# Schematic.net
KiCad netlist of a schematic drawn in EAGLE
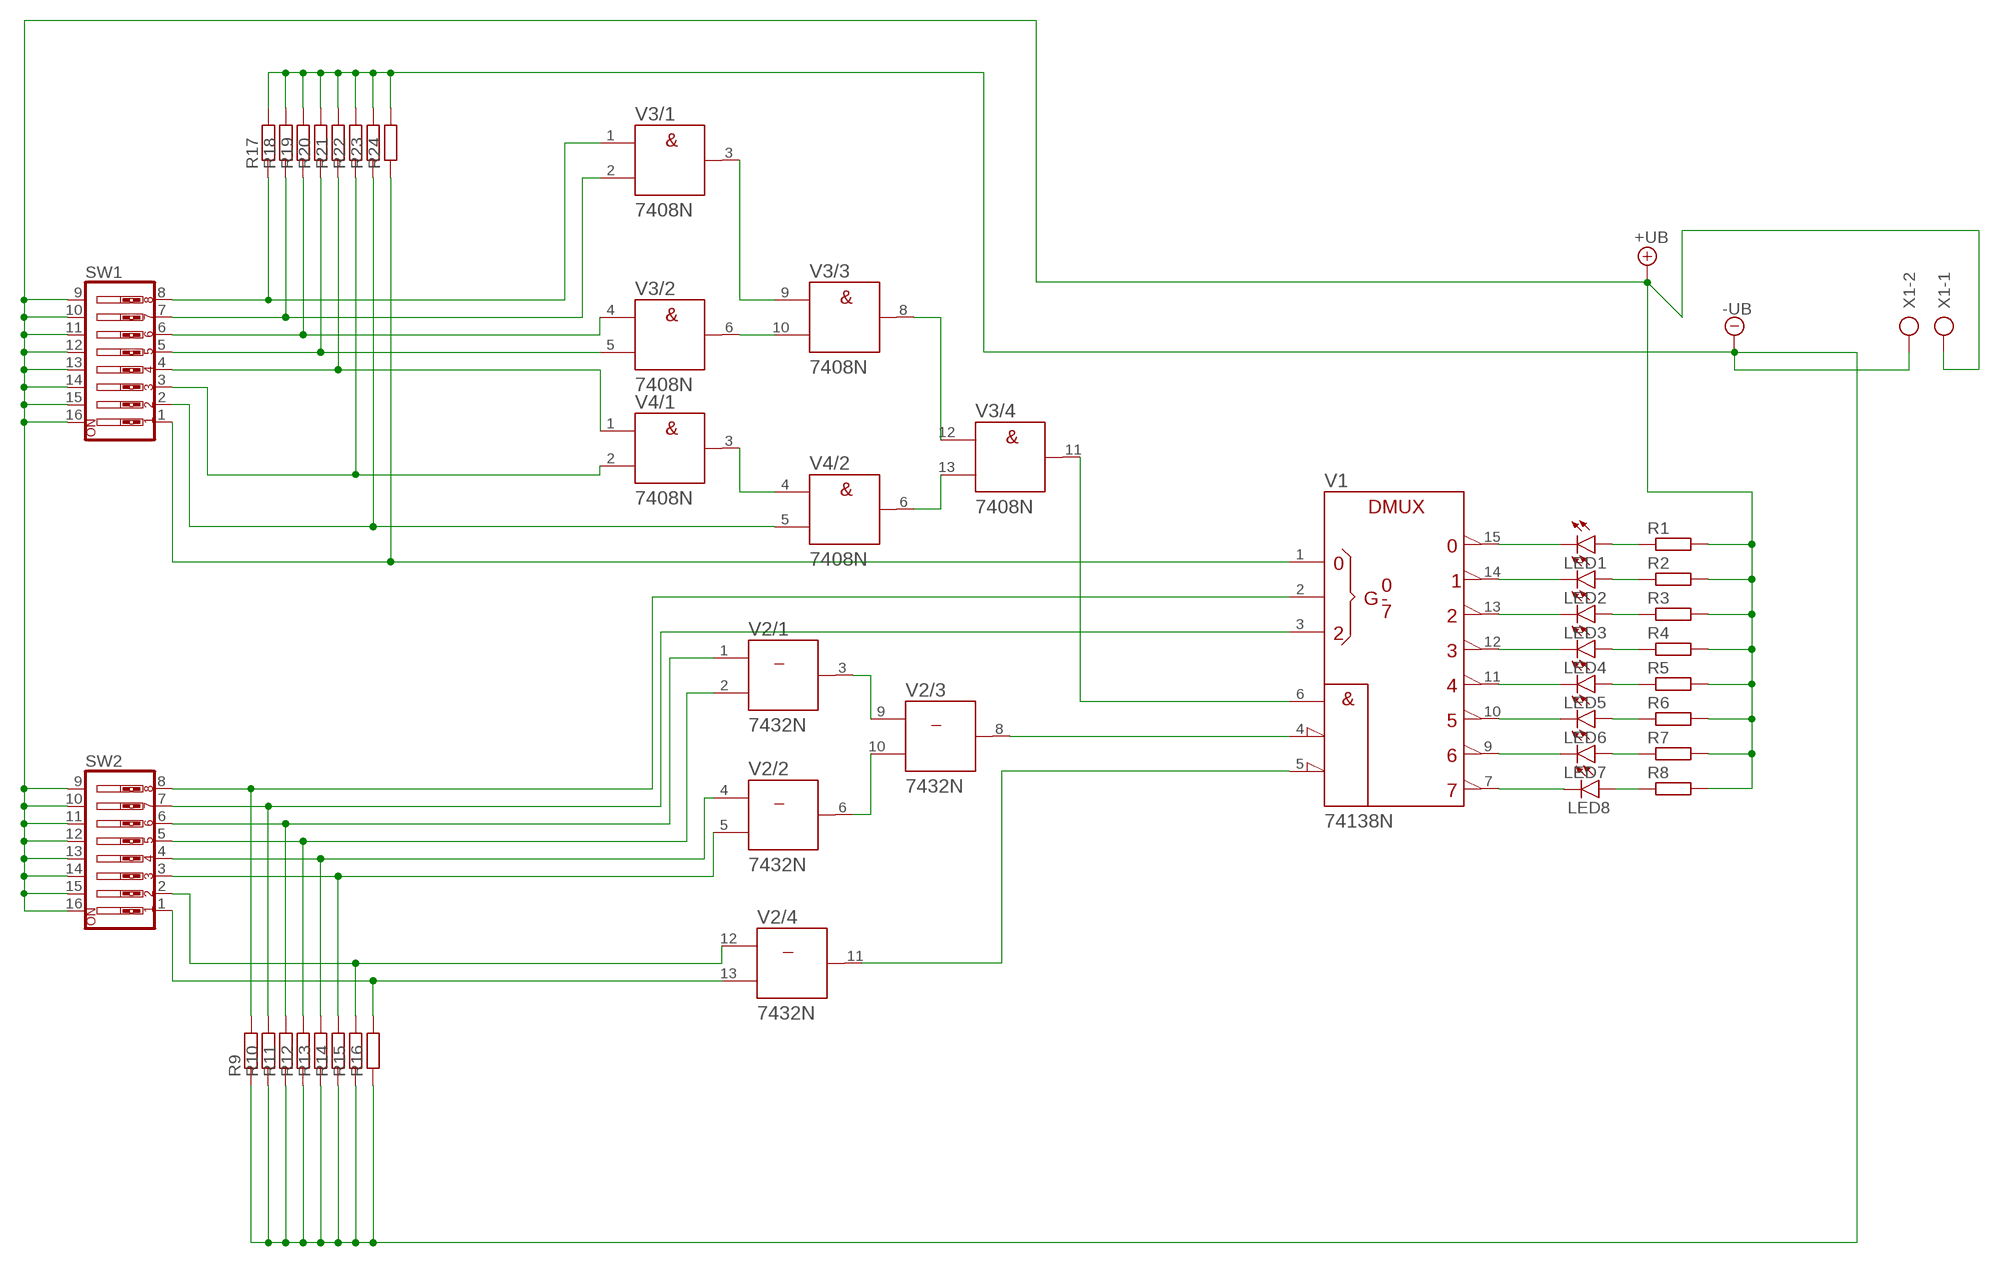
[diagram p0: schematic, sheet 1]

(export (version "E")
  (design (tool "Eeschema 10.0.6"))
  (components
    (comp (ref "LED1")
      (value "LED5MM")
      (footprint "eagle-import:LED5MM")
      (libsource (lib "eagle-import") (part "LED5MM"))
    )
    (comp (ref "LED2")
      (value "LED5MM")
      (footprint "eagle-import:LED5MM")
      (libsource (lib "eagle-import") (part "LED5MM"))
    )
    (comp (ref "LED3")
      (value "LED5MM")
      (footprint "eagle-import:LED5MM")
      (libsource (lib "eagle-import") (part "LED5MM"))
    )
    (comp (ref "LED4")
      (value "LED5MM")
      (footprint "eagle-import:LED5MM")
      (libsource (lib "eagle-import") (part "LED5MM"))
    )
    (comp (ref "LED5")
      (value "LED5MM")
      (footprint "eagle-import:LED5MM")
      (libsource (lib "eagle-import") (part "LED5MM"))
    )
    (comp (ref "LED6")
      (value "LED5MM")
      (footprint "eagle-import:LED5MM")
      (libsource (lib "eagle-import") (part "LED5MM"))
    )
    (comp (ref "LED7")
      (value "LED5MM")
      (footprint "eagle-import:LED5MM")
      (libsource (lib "eagle-import") (part "LED5MM"))
    )
    (comp (ref "LED8")
      (value "LED5MM")
      (footprint "eagle-import:LED5MM")
      (libsource (lib "eagle-import") (part "LED5MM"))
    )
    (comp (ref "R1")
      (value "R-EU_0207/10")
      (footprint "eagle-import:0207_10")
      (libsource (lib "eagle-import") (part "R-EU_0207/10"))
    )
    (comp (ref "R2")
      (value "R-EU_0207/10")
      (footprint "eagle-import:0207_10")
      (libsource (lib "eagle-import") (part "R-EU_0207/10"))
    )
    (comp (ref "R3")
      (value "R-EU_0207/10")
      (footprint "eagle-import:0207_10")
      (libsource (lib "eagle-import") (part "R-EU_0207/10"))
    )
    (comp (ref "R4")
      (value "R-EU_0207/10")
      (footprint "eagle-import:0207_10")
      (libsource (lib "eagle-import") (part "R-EU_0207/10"))
    )
    (comp (ref "R5")
      (value "R-EU_0207/10")
      (footprint "eagle-import:0207_10")
      (libsource (lib "eagle-import") (part "R-EU_0207/10"))
    )
    (comp (ref "R6")
      (value "R-EU_0207/10")
      (footprint "eagle-import:0207_10")
      (libsource (lib "eagle-import") (part "R-EU_0207/10"))
    )
    (comp (ref "R7")
      (value "R-EU_0207/10")
      (footprint "eagle-import:0207_10")
      (libsource (lib "eagle-import") (part "R-EU_0207/10"))
    )
    (comp (ref "R8")
      (value "R-EU_0207/10")
      (footprint "eagle-import:0207_10")
      (libsource (lib "eagle-import") (part "R-EU_0207/10"))
    )
    (comp (ref "R9")
      (value "R-EU_0207/10")
      (footprint "eagle-import:0207_10")
      (libsource (lib "eagle-import") (part "R-EU_0207/10"))
    )
    (comp (ref "R10")
      (value "R-EU_0207/10")
      (footprint "eagle-import:0207_10")
      (libsource (lib "eagle-import") (part "R-EU_0207/10"))
    )
    (comp (ref "R11")
      (value "R-EU_0207/10")
      (footprint "eagle-import:0207_10")
      (libsource (lib "eagle-import") (part "R-EU_0207/10"))
    )
    (comp (ref "R12")
      (value "R-EU_0207/10")
      (footprint "eagle-import:0207_10")
      (libsource (lib "eagle-import") (part "R-EU_0207/10"))
    )
    (comp (ref "R13")
      (value "R-EU_0207/10")
      (footprint "eagle-import:0207_10")
      (libsource (lib "eagle-import") (part "R-EU_0207/10"))
    )
    (comp (ref "R14")
      (value "R-EU_0207/10")
      (footprint "eagle-import:0207_10")
      (libsource (lib "eagle-import") (part "R-EU_0207/10"))
    )
    (comp (ref "R15")
      (value "R-EU_0207/10")
      (footprint "eagle-import:0207_10")
      (libsource (lib "eagle-import") (part "R-EU_0207/10"))
    )
    (comp (ref "R16")
      (value "R-EU_0207/10")
      (footprint "eagle-import:0207_10")
      (libsource (lib "eagle-import") (part "R-EU_0207/10"))
    )
    (comp (ref "R17")
      (value "R-EU_0207/10")
      (footprint "eagle-import:0207_10")
      (libsource (lib "eagle-import") (part "R-EU_0207/10"))
    )
    (comp (ref "R18")
      (value "R-EU_0207/10")
      (footprint "eagle-import:0207_10")
      (libsource (lib "eagle-import") (part "R-EU_0207/10"))
    )
    (comp (ref "R19")
      (value "R-EU_0207/10")
      (footprint "eagle-import:0207_10")
      (libsource (lib "eagle-import") (part "R-EU_0207/10"))
    )
    (comp (ref "R20")
      (value "R-EU_0207/10")
      (footprint "eagle-import:0207_10")
      (libsource (lib "eagle-import") (part "R-EU_0207/10"))
    )
    (comp (ref "R21")
      (value "R-EU_0207/10")
      (footprint "eagle-import:0207_10")
      (libsource (lib "eagle-import") (part "R-EU_0207/10"))
    )
    (comp (ref "R22")
      (value "R-EU_0207/10")
      (footprint "eagle-import:0207_10")
      (libsource (lib "eagle-import") (part "R-EU_0207/10"))
    )
    (comp (ref "R23")
      (value "R-EU_0207/10")
      (footprint "eagle-import:0207_10")
      (libsource (lib "eagle-import") (part "R-EU_0207/10"))
    )
    (comp (ref "R24")
      (value "R-EU_0207/10")
      (footprint "eagle-import:0207_10")
      (libsource (lib "eagle-import") (part "R-EU_0207/10"))
    )
    (comp (ref "SW1")
      (value "SW_DIP-8")
      (footprint "eagle-import:EDG-08")
      (libsource (lib "eagle-import") (part "SW_DIP-8"))
    )
    (comp (ref "SW2")
      (value "SW_DIP-8")
      (footprint "eagle-import:EDG-08")
      (libsource (lib "eagle-import") (part "SW_DIP-8"))
    )
    (comp (ref "V1")
      (value "74138N")
      (footprint "eagle-import:DIL16")
      (libsource (lib "eagle-import") (part "74138N"))
    )
    (comp (ref "V2")
      (value "7432N")
      (footprint "eagle-import:DIL14")
      (libsource (lib "eagle-import") (part "7432N"))
    )
    (comp (ref "V3")
      (value "7408N")
      (footprint "eagle-import:DIL14")
      (libsource (lib "eagle-import") (part "7408N"))
    )
    (comp (ref "V4")
      (value "7408N")
      (footprint "eagle-import:DIL14")
      (libsource (lib "eagle-import") (part "7408N"))
    )
    (comp (ref "X1")
      (value "AK500/2")
      (footprint "eagle-import:AK500_2")
      (libsource (lib "eagle-import") (part "AK500/2"))
    )
  )
  (nets
    (net (code "1") (name "+UB") (class "Default")
      (node (ref "R1") (pin "2") (pinfunction "2_2") (pintype "passive"))
      (node (ref "R2") (pin "2") (pinfunction "2_2") (pintype "passive"))
      (node (ref "R3") (pin "2") (pinfunction "2_2") (pintype "passive"))
      (node (ref "R4") (pin "2") (pinfunction "2_2") (pintype "passive"))
      (node (ref "R5") (pin "2") (pinfunction "2_2") (pintype "passive"))
      (node (ref "R6") (pin "2") (pinfunction "2_2") (pintype "passive"))
      (node (ref "R7") (pin "2") (pinfunction "2_2") (pintype "passive"))
      (node (ref "R8") (pin "2") (pinfunction "2_2") (pintype "passive"))
      (node (ref "SW1") (pin "10") (pinfunction "10_10") (pintype "passive"))
      (node (ref "SW1") (pin "11") (pinfunction "11_11") (pintype "passive"))
      (node (ref "SW1") (pin "12") (pinfunction "12_12") (pintype "passive"))
      (node (ref "SW1") (pin "13") (pinfunction "13_13") (pintype "passive"))
      (node (ref "SW1") (pin "14") (pinfunction "14_14") (pintype "passive"))
      (node (ref "SW1") (pin "15") (pinfunction "15_15") (pintype "passive"))
      (node (ref "SW1") (pin "16") (pinfunction "16_16") (pintype "passive"))
      (node (ref "SW1") (pin "9") (pinfunction "9_9") (pintype "passive"))
      (node (ref "SW2") (pin "10") (pinfunction "10_10") (pintype "passive"))
      (node (ref "SW2") (pin "11") (pinfunction "11_11") (pintype "passive"))
      (node (ref "SW2") (pin "12") (pinfunction "12_12") (pintype "passive"))
      (node (ref "SW2") (pin "13") (pinfunction "13_13") (pintype "passive"))
      (node (ref "SW2") (pin "14") (pinfunction "14_14") (pintype "passive"))
      (node (ref "SW2") (pin "15") (pinfunction "15_15") (pintype "passive"))
      (node (ref "SW2") (pin "16") (pinfunction "16_16") (pintype "passive"))
      (node (ref "SW2") (pin "9") (pinfunction "9_9") (pintype "passive"))
      (node (ref "X1") (pin "1") (pinfunction "KL_1") (pintype "passive"))
    )
    (net (code "2") (name "-UB") (class "Default")
      (node (ref "R10") (pin "1") (pinfunction "1_1") (pintype "passive"))
      (node (ref "R11") (pin "1") (pinfunction "1_1") (pintype "passive"))
      (node (ref "R12") (pin "1") (pinfunction "1_1") (pintype "passive"))
      (node (ref "R13") (pin "1") (pinfunction "1_1") (pintype "passive"))
      (node (ref "R14") (pin "1") (pinfunction "1_1") (pintype "passive"))
      (node (ref "R15") (pin "1") (pinfunction "1_1") (pintype "passive"))
      (node (ref "R16") (pin "1") (pinfunction "1_1") (pintype "passive"))
      (node (ref "R17") (pin "2") (pinfunction "2_2") (pintype "passive"))
      (node (ref "R18") (pin "2") (pinfunction "2_2") (pintype "passive"))
      (node (ref "R19") (pin "2") (pinfunction "2_2") (pintype "passive"))
      (node (ref "R20") (pin "2") (pinfunction "2_2") (pintype "passive"))
      (node (ref "R21") (pin "2") (pinfunction "2_2") (pintype "passive"))
      (node (ref "R22") (pin "2") (pinfunction "2_2") (pintype "passive"))
      (node (ref "R23") (pin "2") (pinfunction "2_2") (pintype "passive"))
      (node (ref "R24") (pin "2") (pinfunction "2_2") (pintype "passive"))
      (node (ref "R9") (pin "1") (pinfunction "1_1") (pintype "passive"))
      (node (ref "X1") (pin "2") (pinfunction "KL_2") (pintype "passive"))
    )
    (net (code "3") (name "Net-(LED1-C)") (class "Default")
      (node (ref "LED1") (pin "K") (pinfunction "C_K") (pintype "passive"))
      (node (ref "V1") (pin "15") (pinfunction "Y0_15") (pintype "output"))
    )
    (net (code "4") (name "Net-(LED1-PadA)") (class "Default")
      (node (ref "LED1") (pin "A") (pinfunction "A_A") (pintype "passive"))
      (node (ref "R1") (pin "1") (pinfunction "1_1") (pintype "passive"))
    )
    (net (code "5") (name "Net-(LED2-C)") (class "Default")
      (node (ref "LED2") (pin "K") (pinfunction "C_K") (pintype "passive"))
      (node (ref "V1") (pin "14") (pinfunction "Y1_14") (pintype "output"))
    )
    (net (code "6") (name "Net-(LED2-PadA)") (class "Default")
      (node (ref "LED2") (pin "A") (pinfunction "A_A") (pintype "passive"))
      (node (ref "R2") (pin "1") (pinfunction "1_1") (pintype "passive"))
    )
    (net (code "7") (name "Net-(LED3-C)") (class "Default")
      (node (ref "LED3") (pin "K") (pinfunction "C_K") (pintype "passive"))
      (node (ref "V1") (pin "13") (pinfunction "Y2_13") (pintype "output"))
    )
    (net (code "8") (name "Net-(LED3-PadA)") (class "Default")
      (node (ref "LED3") (pin "A") (pinfunction "A_A") (pintype "passive"))
      (node (ref "R3") (pin "1") (pinfunction "1_1") (pintype "passive"))
    )
    (net (code "9") (name "Net-(LED4-C)") (class "Default")
      (node (ref "LED4") (pin "K") (pinfunction "C_K") (pintype "passive"))
      (node (ref "V1") (pin "12") (pinfunction "Y3_12") (pintype "output"))
    )
    (net (code "10") (name "Net-(LED4-PadA)") (class "Default")
      (node (ref "LED4") (pin "A") (pinfunction "A_A") (pintype "passive"))
      (node (ref "R4") (pin "1") (pinfunction "1_1") (pintype "passive"))
    )
    (net (code "11") (name "Net-(LED5-C)") (class "Default")
      (node (ref "LED5") (pin "K") (pinfunction "C_K") (pintype "passive"))
      (node (ref "V1") (pin "11") (pinfunction "Y4_11") (pintype "output"))
    )
    (net (code "12") (name "Net-(LED5-PadA)") (class "Default")
      (node (ref "LED5") (pin "A") (pinfunction "A_A") (pintype "passive"))
      (node (ref "R5") (pin "1") (pinfunction "1_1") (pintype "passive"))
    )
    (net (code "13") (name "Net-(LED6-C)") (class "Default")
      (node (ref "LED6") (pin "K") (pinfunction "C_K") (pintype "passive"))
      (node (ref "V1") (pin "10") (pinfunction "Y5_10") (pintype "output"))
    )
    (net (code "14") (name "Net-(LED6-PadA)") (class "Default")
      (node (ref "LED6") (pin "A") (pinfunction "A_A") (pintype "passive"))
      (node (ref "R6") (pin "1") (pinfunction "1_1") (pintype "passive"))
    )
    (net (code "15") (name "Net-(LED7-C)") (class "Default")
      (node (ref "LED7") (pin "K") (pinfunction "C_K") (pintype "passive"))
      (node (ref "V1") (pin "9") (pinfunction "Y6_9") (pintype "output"))
    )
    (net (code "16") (name "Net-(LED7-PadA)") (class "Default")
      (node (ref "LED7") (pin "A") (pinfunction "A_A") (pintype "passive"))
      (node (ref "R7") (pin "1") (pinfunction "1_1") (pintype "passive"))
    )
    (net (code "17") (name "Net-(LED8-C)") (class "Default")
      (node (ref "LED8") (pin "K") (pinfunction "C_K") (pintype "passive"))
      (node (ref "V1") (pin "7") (pinfunction "Y7_7") (pintype "output"))
    )
    (net (code "18") (name "Net-(LED8-PadA)") (class "Default")
      (node (ref "LED8") (pin "A") (pinfunction "A_A") (pintype "passive"))
      (node (ref "R8") (pin "1") (pinfunction "1_1") (pintype "passive"))
    )
    (net (code "19") (name "Net-(V1C-A)") (class "Default")
      (node (ref "R24") (pin "1") (pinfunction "1_1") (pintype "passive"))
      (node (ref "SW1") (pin "1") (pinfunction "1_1") (pintype "passive"))
      (node (ref "V1") (pin "1") (pinfunction "A_1") (pintype "input"))
    )
    (net (code "20") (name "Net-(V1C-B)") (class "Default")
      (node (ref "R9") (pin "2") (pinfunction "2_2") (pintype "passive"))
      (node (ref "SW2") (pin "8") (pinfunction "8_8") (pintype "passive"))
      (node (ref "V1") (pin "2") (pinfunction "B_2") (pintype "input"))
    )
    (net (code "21") (name "Net-(V1C-C)") (class "Default")
      (node (ref "R10") (pin "2") (pinfunction "2_2") (pintype "passive"))
      (node (ref "SW2") (pin "7") (pinfunction "7_7") (pintype "passive"))
      (node (ref "V1") (pin "3") (pinfunction "C_3") (pintype "input"))
    )
    (net (code "22") (name "Net-(V1C-G1)") (class "Default")
      (node (ref "V1") (pin "6") (pinfunction "G1_6") (pintype "input"))
      (node (ref "V3") (pin "11") (pinfunction "Y_11") (pintype "output"))
    )
    (net (code "23") (name "Net-(V1C-~{G2A})") (class "Default")
      (node (ref "V1") (pin "4") (pinfunction "~{G2A}_4") (pintype "input"))
      (node (ref "V2") (pin "8") (pinfunction "Y_8") (pintype "output"))
    )
    (net (code "24") (name "Net-(V1C-~{G2B})") (class "Default")
      (node (ref "V1") (pin "5") (pinfunction "~{G2B}_5") (pintype "input"))
      (node (ref "V2") (pin "11") (pinfunction "Y_11") (pintype "output"))
    )
    (net (code "25") (name "Net-(V2C-A)") (class "Default")
      (node (ref "R11") (pin "2") (pinfunction "2_2") (pintype "passive"))
      (node (ref "SW2") (pin "6") (pinfunction "6_6") (pintype "passive"))
      (node (ref "V2") (pin "1") (pinfunction "A_1") (pintype "input"))
    )
    (net (code "26") (name "Net-(V2C-B)") (class "Default")
      (node (ref "R12") (pin "2") (pinfunction "2_2") (pintype "passive"))
      (node (ref "SW2") (pin "5") (pinfunction "5_5") (pintype "passive"))
      (node (ref "V2") (pin "2") (pinfunction "B_2") (pintype "input"))
    )
    (net (code "27") (name "Net-(V2C-Y)") (class "Default")
      (node (ref "V2") (pin "3") (pinfunction "Y_3") (pintype "output"))
      (node (ref "V2") (pin "9") (pinfunction "A_9") (pintype "input"))
    )
    (net (code "28") (name "Net-(V2D-A)") (class "Default")
      (node (ref "R13") (pin "2") (pinfunction "2_2") (pintype "passive"))
      (node (ref "SW2") (pin "4") (pinfunction "4_4") (pintype "passive"))
      (node (ref "V2") (pin "4") (pinfunction "A_4") (pintype "input"))
    )
    (net (code "29") (name "Net-(V2D-B)") (class "Default")
      (node (ref "R14") (pin "2") (pinfunction "2_2") (pintype "passive"))
      (node (ref "SW2") (pin "3") (pinfunction "3_3") (pintype "passive"))
      (node (ref "V2") (pin "5") (pinfunction "B_5") (pintype "input"))
    )
    (net (code "30") (name "Net-(V2D-Y)") (class "Default")
      (node (ref "V2") (pin "10") (pinfunction "B_10") (pintype "input"))
      (node (ref "V2") (pin "6") (pinfunction "Y_6") (pintype "output"))
    )
    (net (code "31") (name "Net-(V2F-A)") (class "Default")
      (node (ref "R15") (pin "2") (pinfunction "2_2") (pintype "passive"))
      (node (ref "SW2") (pin "2") (pinfunction "2_2") (pintype "passive"))
      (node (ref "V2") (pin "12") (pinfunction "A_12") (pintype "input"))
    )
    (net (code "32") (name "Net-(V2F-B)") (class "Default")
      (node (ref "R16") (pin "2") (pinfunction "2_2") (pintype "passive"))
      (node (ref "SW2") (pin "1") (pinfunction "1_1") (pintype "passive"))
      (node (ref "V2") (pin "13") (pinfunction "B_13") (pintype "input"))
    )
    (net (code "33") (name "Net-(V3C-A)") (class "Default")
      (node (ref "R17") (pin "1") (pinfunction "1_1") (pintype "passive"))
      (node (ref "SW1") (pin "8") (pinfunction "8_8") (pintype "passive"))
      (node (ref "V3") (pin "1") (pinfunction "A_1") (pintype "input"))
    )
    (net (code "34") (name "Net-(V3C-B)") (class "Default")
      (node (ref "R18") (pin "1") (pinfunction "1_1") (pintype "passive"))
      (node (ref "SW1") (pin "7") (pinfunction "7_7") (pintype "passive"))
      (node (ref "V3") (pin "2") (pinfunction "B_2") (pintype "input"))
    )
    (net (code "35") (name "Net-(V3C-Y)") (class "Default")
      (node (ref "V3") (pin "3") (pinfunction "Y_3") (pintype "output"))
      (node (ref "V3") (pin "9") (pinfunction "A_9") (pintype "input"))
    )
    (net (code "36") (name "Net-(V3D-A)") (class "Default")
      (node (ref "R19") (pin "1") (pinfunction "1_1") (pintype "passive"))
      (node (ref "SW1") (pin "6") (pinfunction "6_6") (pintype "passive"))
      (node (ref "V3") (pin "4") (pinfunction "A_4") (pintype "input"))
    )
    (net (code "37") (name "Net-(V3D-B)") (class "Default")
      (node (ref "R20") (pin "1") (pinfunction "1_1") (pintype "passive"))
      (node (ref "SW1") (pin "5") (pinfunction "5_5") (pintype "passive"))
      (node (ref "V3") (pin "5") (pinfunction "B_5") (pintype "input"))
    )
    (net (code "38") (name "Net-(V3D-Y)") (class "Default")
      (node (ref "V3") (pin "10") (pinfunction "B_10") (pintype "input"))
      (node (ref "V3") (pin "6") (pinfunction "Y_6") (pintype "output"))
    )
    (net (code "39") (name "Net-(V3E-Y)") (class "Default")
      (node (ref "V3") (pin "12") (pinfunction "A_12") (pintype "input"))
      (node (ref "V3") (pin "8") (pinfunction "Y_8") (pintype "output"))
    )
    (net (code "40") (name "Net-(V3F-B)") (class "Default")
      (node (ref "V3") (pin "13") (pinfunction "B_13") (pintype "input"))
      (node (ref "V4") (pin "6") (pinfunction "Y_6") (pintype "output"))
    )
    (net (code "41") (name "Net-(V4C-A)") (class "Default")
      (node (ref "R21") (pin "1") (pinfunction "1_1") (pintype "passive"))
      (node (ref "SW1") (pin "4") (pinfunction "4_4") (pintype "passive"))
      (node (ref "V4") (pin "1") (pinfunction "A_1") (pintype "input"))
    )
    (net (code "42") (name "Net-(V4C-B)") (class "Default")
      (node (ref "R22") (pin "1") (pinfunction "1_1") (pintype "passive"))
      (node (ref "SW1") (pin "3") (pinfunction "3_3") (pintype "passive"))
      (node (ref "V4") (pin "2") (pinfunction "B_2") (pintype "input"))
    )
    (net (code "43") (name "Net-(V4C-Y)") (class "Default")
      (node (ref "V4") (pin "3") (pinfunction "Y_3") (pintype "output"))
      (node (ref "V4") (pin "4") (pinfunction "A_4") (pintype "input"))
    )
    (net (code "44") (name "Net-(V4D-B)") (class "Default")
      (node (ref "R23") (pin "1") (pinfunction "1_1") (pintype "passive"))
      (node (ref "SW1") (pin "2") (pinfunction "2_2") (pintype "passive"))
      (node (ref "V4") (pin "5") (pinfunction "B_5") (pintype "input"))
    )
  )
)
